# GPS-SD.net
KiCad netlist of a schematic drawn in Altium Designer
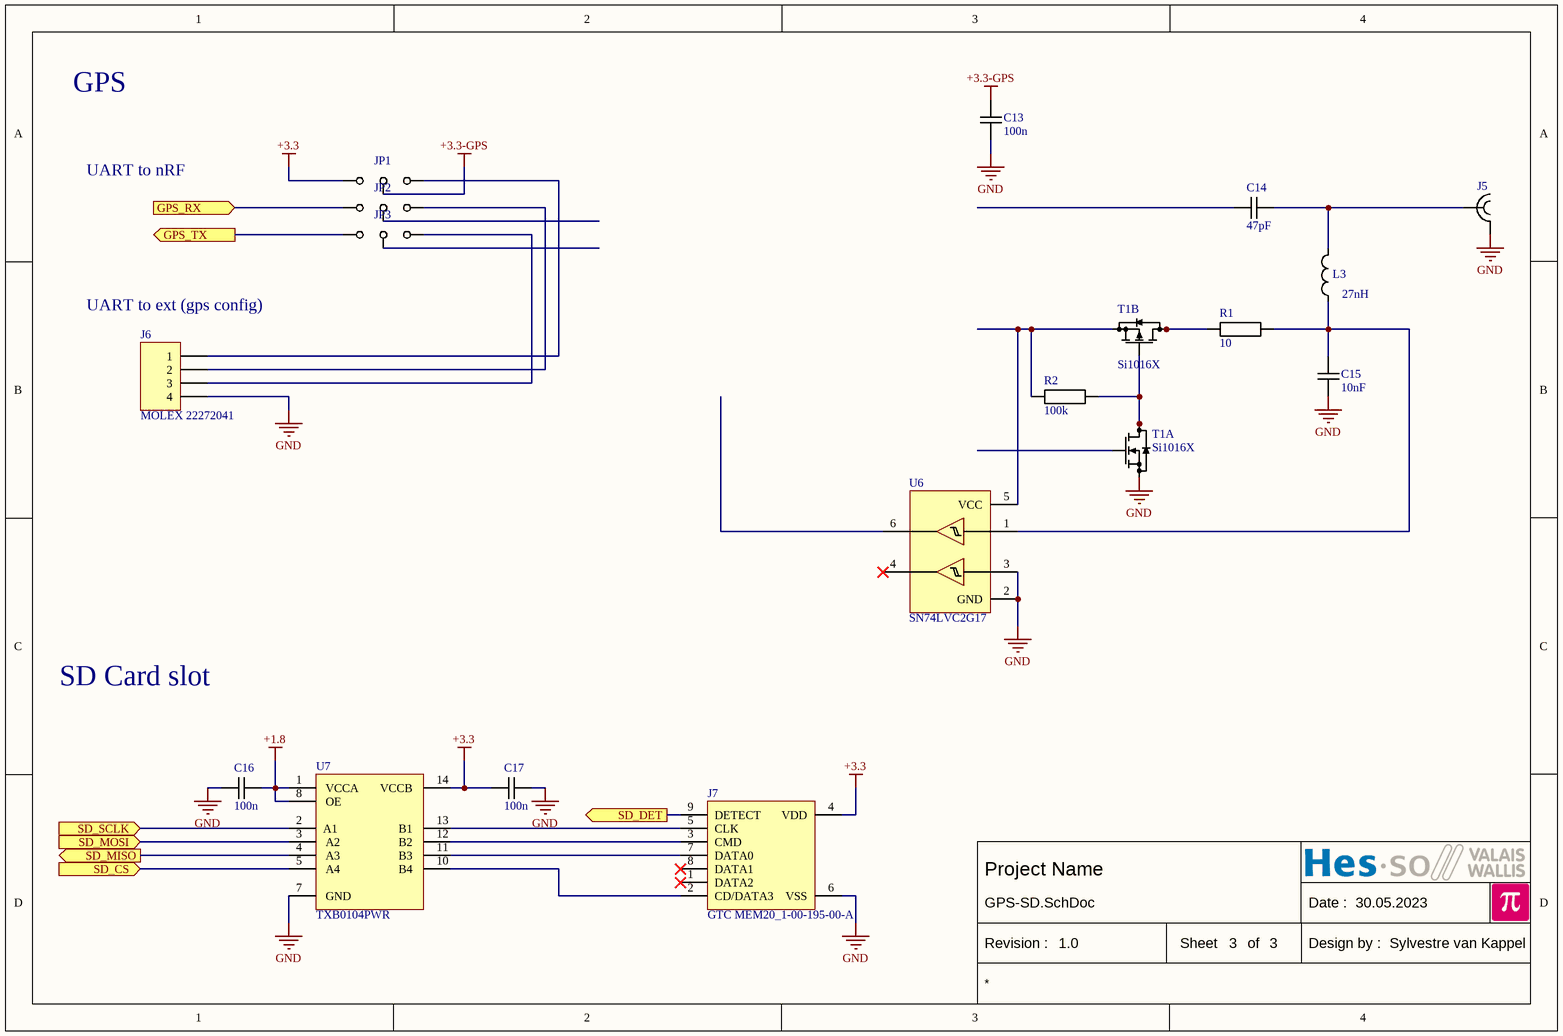
[diagram p0: GPS-SD.SchDoc]

(export (version "E")
  (design (tool "Eeschema 10.0.6"))
  (components
    (comp (ref "C13")
      (value "100n")
      (footprint "CAPACITOR 1608 REFLOW")
      (description "Capacitor")
      (libsource (lib "Capacitor") (part "Capacitor"))
    )
    (comp (ref "C14")
      (value "47pF")
      (footprint "CAPACITOR 1608 REFLOW")
      (description "Capacitor")
      (libsource (lib "Capacitor") (part "Capacitor"))
    )
    (comp (ref "C15")
      (value "10nF")
      (footprint "CAPACITOR 1608 REFLOW")
      (description "Capacitor")
      (libsource (lib "Capacitor") (part "Capacitor"))
    )
    (comp (ref "C16")
      (value "100n")
      (footprint "CAPACITOR 1608 REFLOW")
      (description "Capacitor")
      (libsource (lib "Capacitor") (part "Capacitor"))
    )
    (comp (ref "C17")
      (value "100n")
      (footprint "CAPACITOR 1608 REFLOW")
      (description "Capacitor")
      (libsource (lib "Capacitor") (part "Capacitor"))
    )
    (comp (ref "J5")
      (value "732511150")
      (footprint "SMA EDGE Molex 732511150")
      (description "SMA EDGE Molex 732511150")
      (libsource (lib "Connector") (part "SMA EDGE Molex 732511150"))
    )
    (comp (ref "J6")
      (value "MOLEX 22272041")
      (footprint "MOLEX 22272041")
      (description "KK 254 Wire-to-Board Header, Vertical, 4 Circuits")
      (libsource (lib "Connector") (part "MOLEX 22272041"))
    )
    (comp (ref "J7")
      (value "GTC MEM20_1-00-195-00-A")
      (footprint "SD MICRO GCT MEM2051-00-195-00-A")
      (description "SD Card Micro")
      (fields (field (name "MF") "Global Connector Technology") (field (name "MP") "MEM2051-00-195-00-A"))
      (libsource (lib "Connector") (part "SD-MICRO GTC MEM20_1-00-195-00-A"))
    )
    (comp (ref "JP1")
      (value "{Value}")
      (footprint "JUMPER3 SMD 1608")
      (description "JUMPER 3 POS")
      (libsource (lib "Jumper") (part "JUMPER 3 POS"))
    )
    (comp (ref "JP2")
      (value "{Value}")
      (footprint "JUMPER3 SMD 1608")
      (description "JUMPER 3 POS")
      (libsource (lib "Jumper") (part "JUMPER 3 POS"))
    )
    (comp (ref "JP3")
      (value "{Value}")
      (footprint "JUMPER3 SMD 1608")
      (description "JUMPER 3 POS")
      (libsource (lib "Jumper") (part "JUMPER 3 POS"))
    )
    (comp (ref "L3")
      (value "27nH")
      (footprint "INDUCTOR 1608 REFLOW")
      (description "Inductor")
      (libsource (lib "Inductor") (part "Inductor"))
    )
    (comp (ref "R1")
      (value "10")
      (footprint "RESISTOR 1608 REFLOW")
      (description "Resistor")
      (libsource (lib "Resistor") (part "Resistor"))
    )
    (comp (ref "R2")
      (value "100k")
      (footprint "RESISTOR 1608 REFLOW")
      (description "Resistor")
      (libsource (lib "Resistor") (part "Resistor"))
    )
    (comp (ref "T1")
      (value "Si1016X")
      (footprint "SOT563F P0.5 C1.6x1.2 H0.6")
      (description "Complementary N- and P-Channel 20 V (D-S) MOSFET")
      (libsource (lib "Transistor") (part "Si1016X"))
    )
    (comp (ref "U6")
      (value "SN74LVC2G17")
      (footprint "SOT23-6 P0.95 C1.5x3.0 H1.3")
      (description "Dual Schmitt-Trigger Buffer")
      (libsource (lib "IntegratedCircuit") (part "SN74LVC2G17"))
    )
    (comp (ref "U7")
      (value "TXB0104PWR")
      (footprint "TSSOP14 P0.65 C4.4x5.0 H1.1")
      (libsource (lib "IntegratedCircuit") (part "TXB0104PWR"))
    )
  )
  (nets
    (net (code "1") (name "+1.8") (class "Default")
      (node (ref "C16") (pin "2") (pinfunction "2_2") (pintype "passive"))
      (node (ref "U7") (pin "1") (pinfunction "VCCA_1") (pintype "passive"))
      (node (ref "U7") (pin "8") (pinfunction "OE_8") (pintype "passive"))
    )
    (net (code "2") (name "+3.3") (class "Default")
      (node (ref "C17") (pin "2") (pinfunction "2_2") (pintype "passive"))
      (node (ref "J7") (pin "4") (pinfunction "VDD_4") (pintype "power_in"))
      (node (ref "JP1") (pin "1") (pinfunction "1_1") (pintype "passive"))
      (node (ref "U7") (pin "14") (pinfunction "VCCB_14") (pintype "passive"))
    )
    (net (code "3") (name "+3.3-GPS") (class "Default")
      (node (ref "C13") (pin "2") (pinfunction "2_2") (pintype "passive"))
      (node (ref "JP1") (pin "2") (pinfunction "2_2") (pintype "passive"))
    )
    (net (code "4") (name "/GPS_RX") (class "Default")
      (node (ref "JP2") (pin "1") (pinfunction "1_1") (pintype "passive"))
    )
    (net (code "5") (name "/GPS_TX") (class "Default")
      (node (ref "JP3") (pin "1") (pinfunction "1_1") (pintype "passive"))
    )
    (net (code "6") (name "/SD_CS") (class "Default")
      (node (ref "U7") (pin "5") (pinfunction "A4_5") (pintype "passive"))
    )
    (net (code "7") (name "/SD_DET") (class "Default")
      (node (ref "J7") (pin "9") (pinfunction "DETECT_9") (pintype "passive"))
    )
    (net (code "8") (name "/SD_MISO") (class "Default")
      (node (ref "U7") (pin "4") (pinfunction "A3_4") (pintype "passive"))
    )
    (net (code "9") (name "/SD_MOSI") (class "Default")
      (node (ref "U7") (pin "3") (pinfunction "A2_3") (pintype "passive"))
    )
    (net (code "10") (name "/SD_SCLK") (class "Default")
      (node (ref "U7") (pin "2") (pinfunction "A1_2") (pintype "passive"))
    )
    (net (code "11") (name "GND") (class "Default")
      (node (ref "C13") (pin "1") (pinfunction "1_1") (pintype "passive"))
      (node (ref "C15") (pin "1") (pinfunction "1_1") (pintype "passive"))
      (node (ref "C16") (pin "1") (pinfunction "1_1") (pintype "passive"))
      (node (ref "C17") (pin "1") (pinfunction "1_1") (pintype "passive"))
      (node (ref "J5") (pin "2") (pinfunction "2_2") (pintype "passive"))
      (node (ref "J6") (pin "4") (pinfunction "4_4") (pintype "passive"))
      (node (ref "J7") (pin "6") (pinfunction "VSS_6") (pintype "power_in"))
      (node (ref "T1") (pin "1") (pinfunction "S1_1") (pintype "passive"))
      (node (ref "U6") (pin "2") (pinfunction "GND_2") (pintype "passive"))
      (node (ref "U6") (pin "3") (pinfunction "2A_3") (pintype "passive"))
      (node (ref "U7") (pin "7") (pinfunction "GND_7") (pintype "passive"))
    )
    (net (code "12") (name "Net-(C14-Pad1)") (class "Default")
      (node (ref "C14") (pin "1") (pinfunction "1_1") (pintype "passive"))
      (node (ref "J5") (pin "1") (pinfunction "1_1") (pintype "passive"))
      (node (ref "L3") (pin "2") (pinfunction "2_2") (pintype "passive"))
    )
    (net (code "13") (name "Net-(J6-Pad1)") (class "Default")
      (node (ref "J6") (pin "1") (pinfunction "1_1") (pintype "passive"))
      (node (ref "JP1") (pin "3") (pinfunction "3_3") (pintype "passive"))
    )
    (net (code "14") (name "Net-(J6-Pad2)") (class "Default")
      (node (ref "J6") (pin "2") (pinfunction "2_2") (pintype "passive"))
      (node (ref "JP2") (pin "3") (pinfunction "3_3") (pintype "passive"))
    )
    (net (code "15") (name "Net-(J6-Pad3)") (class "Default")
      (node (ref "J6") (pin "3") (pinfunction "3_3") (pintype "passive"))
      (node (ref "JP3") (pin "3") (pinfunction "3_3") (pintype "passive"))
    )
    (net (code "16") (name "Net-(J7-CD{slash}DATA3)") (class "Default")
      (node (ref "J7") (pin "2") (pinfunction "CD/DATA3_2") (pintype "passive"))
      (node (ref "U7") (pin "10") (pinfunction "B4_10") (pintype "passive"))
    )
    (net (code "17") (name "Net-(J7-CLK)") (class "Default")
      (node (ref "J7") (pin "5") (pinfunction "CLK_5") (pintype "passive"))
      (node (ref "U7") (pin "13") (pinfunction "B1_13") (pintype "passive"))
    )
    (net (code "18") (name "Net-(J7-CMD)") (class "Default")
      (node (ref "J7") (pin "3") (pinfunction "CMD_3") (pintype "passive"))
      (node (ref "U7") (pin "12") (pinfunction "B2_12") (pintype "passive"))
    )
    (net (code "19") (name "Net-(J7-DATA0)") (class "Default")
      (node (ref "J7") (pin "7") (pinfunction "DATA0_7") (pintype "passive"))
      (node (ref "U7") (pin "11") (pinfunction "B3_11") (pintype "passive"))
    )
    (net (code "20") (name "Net-(R1-Pad1)") (class "Default")
      (node (ref "R1") (pin "1") (pinfunction "1_1") (pintype "passive"))
      (node (ref "T1") (pin "3") (pinfunction "D2_3") (pintype "passive"))
      (node (ref "T1") (pin "5") (pinfunction "D2_5") (pintype "passive"))
    )
    (net (code "21") (name "Net-(T1B-G2)") (class "Default")
      (node (ref "R2") (pin "2") (pinfunction "2_2") (pintype "passive"))
      (node (ref "T1") (pin "5") (pinfunction "G2_5") (pintype "passive"))
      (node (ref "T1") (pin "6") (pinfunction "D1_6") (pintype "passive"))
      (node (ref "T1") (pin "7") (pinfunction "D1_7") (pintype "passive"))
    )
    (net (code "22") (name "Net-(T1B-S2)") (class "Default")
      (node (ref "R2") (pin "1") (pinfunction "1_1") (pintype "passive"))
      (node (ref "T1") (pin "4") (pinfunction "S2_4") (pintype "passive"))
      (node (ref "U6") (pin "5") (pinfunction "VCC_5") (pintype "passive"))
    )
    (net (code "23") (name "Net-(U6-1A)") (class "Default")
      (node (ref "C15") (pin "2") (pinfunction "2_2") (pintype "passive"))
      (node (ref "L3") (pin "1") (pinfunction "1_1") (pintype "passive"))
      (node (ref "R1") (pin "2") (pinfunction "2_2") (pintype "passive"))
      (node (ref "U6") (pin "1") (pinfunction "1A_1") (pintype "passive"))
    )
    (net (code "24") (name "unconnected-(C14-Pad2)") (class "Default")
      (node (ref "C14") (pin "2") (pinfunction "2_2") (pintype "passive"))
    )
    (net (code "25") (name "unconnected-(J7-DATA1-Pad8)") (class "Default")
      (node (ref "J7") (pin "8") (pinfunction "DATA1_8") (pintype "passive+no_connect"))
    )
    (net (code "26") (name "unconnected-(J7-DATA2-Pad1)") (class "Default")
      (node (ref "J7") (pin "1") (pinfunction "DATA2_1") (pintype "passive+no_connect"))
    )
    (net (code "27") (name "unconnected-(JP2-Pad2)") (class "Default")
      (node (ref "JP2") (pin "2") (pinfunction "2_2") (pintype "passive"))
    )
    (net (code "28") (name "unconnected-(JP3-Pad2)") (class "Default")
      (node (ref "JP3") (pin "2") (pinfunction "2_2") (pintype "passive"))
    )
    (net (code "29") (name "unconnected-(T1A-G1-Pad2)") (class "Default")
      (node (ref "T1") (pin "2") (pinfunction "G1_2") (pintype "passive"))
    )
    (net (code "30") (name "unconnected-(U6-1Y-Pad6)") (class "Default")
      (node (ref "U6") (pin "6") (pinfunction "1Y_6") (pintype "passive"))
    )
    (net (code "31") (name "unconnected-(U6-2Y-Pad4)") (class "Default")
      (node (ref "U6") (pin "4") (pinfunction "2Y_4") (pintype "passive+no_connect"))
    )
  )
)
